# PiPico_Headless.net
KiCad netlist of a schematic drawn in EAGLE
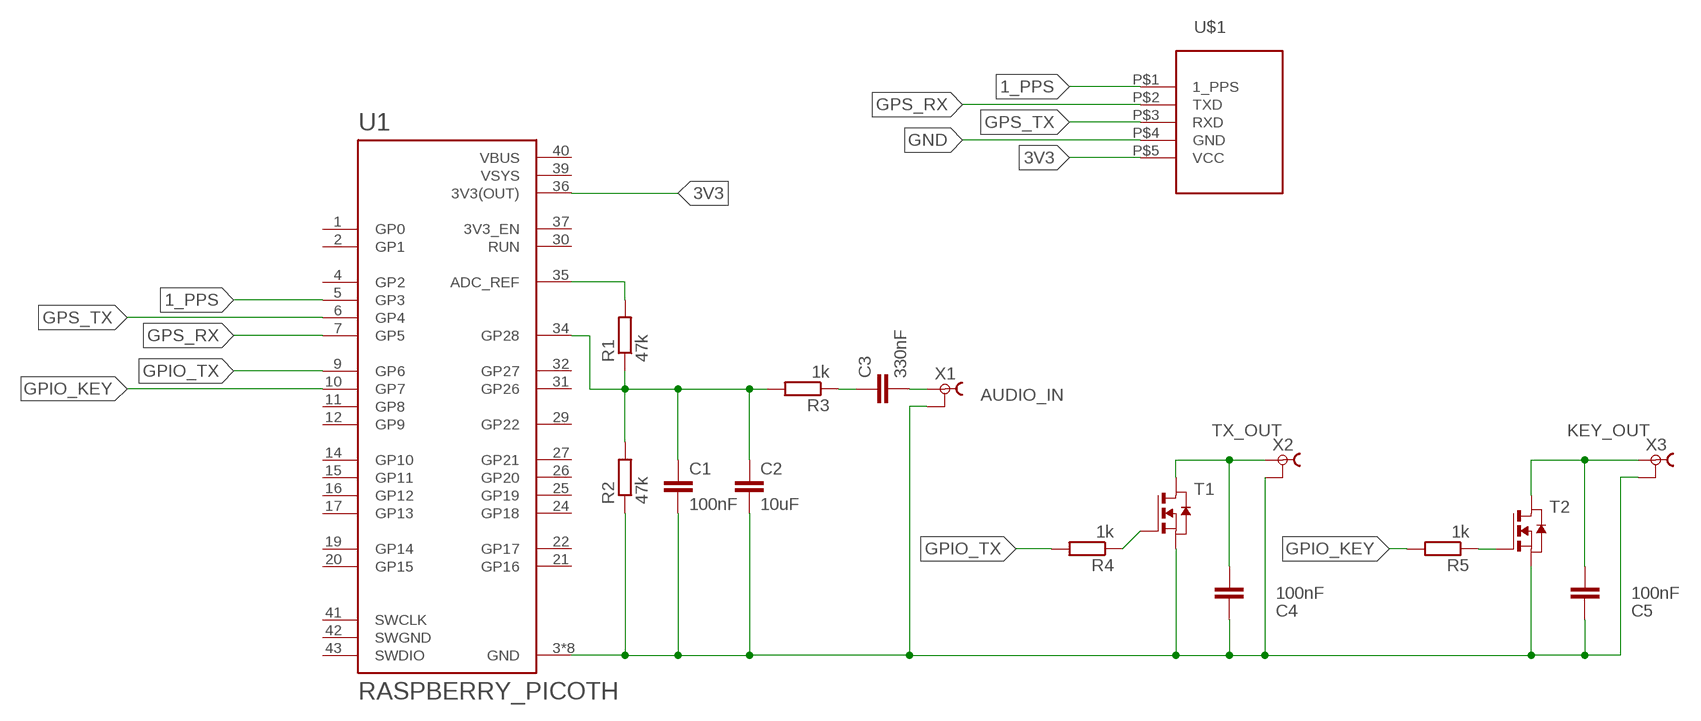
[diagram p0: schematic, sheet 1]

(export (version "E")
  (design (tool "Eeschema 10.0.6"))
  (components
    (comp (ref "C1")
      (value "100nF")
      (footprint "eagle-import:C0805")
      (libsource (lib "eagle-import") (part "C-EUC0805"))
    )
    (comp (ref "C2")
      (value "10uF")
      (footprint "eagle-import:C0805")
      (libsource (lib "eagle-import") (part "C-EUC0805"))
    )
    (comp (ref "C3")
      (value "330nF")
      (footprint "eagle-import:C0805")
      (libsource (lib "eagle-import") (part "C-EUC0805"))
    )
    (comp (ref "C4")
      (value "100nF")
      (footprint "eagle-import:C0805")
      (libsource (lib "eagle-import") (part "C-EUC0805"))
    )
    (comp (ref "C5")
      (value "100nF")
      (footprint "eagle-import:C0805")
      (libsource (lib "eagle-import") (part "C-EUC0805"))
    )
    (comp (ref "R1")
      (value "47k")
      (footprint "eagle-import:R0805")
      (libsource (lib "eagle-import") (part "R-EU_R0805"))
    )
    (comp (ref "R2")
      (value "47k")
      (footprint "eagle-import:R0805")
      (libsource (lib "eagle-import") (part "R-EU_R0805"))
    )
    (comp (ref "R3")
      (value "1k")
      (footprint "eagle-import:R0805")
      (libsource (lib "eagle-import") (part "R-EU_R0805"))
    )
    (comp (ref "R4")
      (value "1k")
      (footprint "eagle-import:R0805")
      (libsource (lib "eagle-import") (part "R-EU_R0805"))
    )
    (comp (ref "R5")
      (value "1k")
      (footprint "eagle-import:R0805")
      (libsource (lib "eagle-import") (part "R-EU_R0805"))
    )
    (comp (ref "T1")
      (value "NMOSSOT23")
      (footprint "eagle-import:SOT-23")
      (libsource (lib "eagle-import") (part "NMOSSOT23"))
    )
    (comp (ref "T2")
      (value "NMOSSOT23")
      (footprint "eagle-import:SOT-23")
      (libsource (lib "eagle-import") (part "NMOSSOT23"))
    )
    (comp (ref "U$1")
      (value "GPS")
      (footprint "eagle-import:GPS")
      (libsource (lib "eagle-import") (part "GPS"))
    )
    (comp (ref "U1")
      (value "RASPBERRY_PICOTH")
      (footprint "eagle-import:PICO-PKG-TH")
      (libsource (lib "eagle-import") (part "RASPBERRY_PICOTH"))
    )
    (comp (ref "X1")
      (value "AUDIO_IN")
      (footprint "eagle-import:TOBU3")
      (fields (field (name "MF") "FARNELL") (field (name "MPN") "TOBU 3"))
      (libsource (lib "eagle-import") (part "TOBU3"))
    )
    (comp (ref "X2")
      (value "TX_OUT")
      (footprint "eagle-import:TOBU3")
      (fields (field (name "MF") "FARNELL") (field (name "MPN") "TOBU 3"))
      (libsource (lib "eagle-import") (part "TOBU3"))
    )
    (comp (ref "X3")
      (value "KEY_OUT")
      (footprint "eagle-import:TOBU3")
      (fields
        (field (name "MF") "FARNELL")
        (field (name "MPN") "TOBU 3")
        (field (name "MF_1") "FARNELL")
        (field (name "MPN_1") "TOBU 3")
        (field (name "OC_FARNELL") "592791")
        (field (name "OC_NEWARK") "06WX5914")
      )
      (libsource (lib "eagle-import") (part "TOBU3"))
    )
  )
  (nets
    (net (code "1") (name "/SWGND") (class "Default")
      (node (ref "U1") (pin "42") (pinfunction "SWGND_42") (pintype "power_in"))
    )
    (net (code "2") (name "/VBUS") (class "Default")
      (node (ref "U1") (pin "40") (pinfunction "VBUS_40") (pintype "power_in"))
    )
    (net (code "3") (name "/VSYS") (class "Default")
      (node (ref "U1") (pin "39") (pinfunction "VSYS_39") (pintype "power_in"))
    )
    (net (code "4") (name "1_PPS") (class "Default")
      (node (ref "U$1") (pin "P$1") (pinfunction "1_PPS_P$1") (pintype "bidirectional"))
      (node (ref "U1") (pin "5") (pinfunction "GP3_5") (pintype "bidirectional"))
    )
    (net (code "5") (name "3V3") (class "Default")
      (node (ref "U$1") (pin "P$5") (pinfunction "VCC_P$5") (pintype "bidirectional"))
      (node (ref "U1") (pin "36") (pinfunction "3V3(OUT)_36") (pintype "power_in"))
    )
    (net (code "6") (name "GND") (class "Default")
      (node (ref "C1") (pin "2") (pinfunction "2_2") (pintype "passive"))
      (node (ref "C2") (pin "2") (pinfunction "2_2") (pintype "passive"))
      (node (ref "C4") (pin "1") (pinfunction "1_1") (pintype "passive"))
      (node (ref "C5") (pin "1") (pinfunction "1_1") (pintype "passive"))
      (node (ref "R2") (pin "1") (pinfunction "1_1") (pintype "passive"))
      (node (ref "T1") (pin "2") (pinfunction "S_2") (pintype "passive"))
      (node (ref "T2") (pin "2") (pinfunction "S_2") (pintype "passive"))
      (node (ref "U$1") (pin "P$4") (pinfunction "GND_P$4") (pintype "bidirectional"))
      (node (ref "U1") (pin "13") (pinfunction "GND_13") (pintype "power_in"))
      (node (ref "U1") (pin "18") (pinfunction "GND_18") (pintype "power_in"))
      (node (ref "U1") (pin "23") (pinfunction "GND_23") (pintype "power_in"))
      (node (ref "U1") (pin "28") (pinfunction "GND_28") (pintype "power_in"))
      (node (ref "U1") (pin "3") (pinfunction "GND_3") (pintype "power_in"))
      (node (ref "U1") (pin "33") (pinfunction "GND_33") (pintype "power_in"))
      (node (ref "U1") (pin "38") (pinfunction "GND_38") (pintype "power_in"))
      (node (ref "U1") (pin "8") (pinfunction "GND_8") (pintype "power_in"))
      (node (ref "X1") (pin "2") (pinfunction "2_2") (pintype "passive"))
      (node (ref "X1") (pin "2@1") (pinfunction "2_2@1") (pintype "passive"))
      (node (ref "X1") (pin "2@2") (pinfunction "2_2@2") (pintype "passive"))
      (node (ref "X2") (pin "2") (pinfunction "2_2") (pintype "passive"))
      (node (ref "X2") (pin "2@1") (pinfunction "2_2@1") (pintype "passive"))
      (node (ref "X2") (pin "2@2") (pinfunction "2_2@2") (pintype "passive"))
      (node (ref "X3") (pin "2") (pinfunction "2_2") (pintype "passive"))
      (node (ref "X3") (pin "2@1") (pinfunction "2_2@1") (pintype "passive"))
      (node (ref "X3") (pin "2@2") (pinfunction "2_2@2") (pintype "passive"))
    )
    (net (code "7") (name "GPIO_KEY") (class "Default")
      (node (ref "R5") (pin "2") (pinfunction "2_2") (pintype "passive"))
      (node (ref "U1") (pin "10") (pinfunction "GP7_10") (pintype "bidirectional"))
    )
    (net (code "8") (name "GPIO_TX") (class "Default")
      (node (ref "R4") (pin "2") (pinfunction "2_2") (pintype "passive"))
      (node (ref "U1") (pin "9") (pinfunction "GP6_9") (pintype "bidirectional"))
    )
    (net (code "9") (name "GPS_RX") (class "Default")
      (node (ref "U$1") (pin "P$2") (pinfunction "TXD_P$2") (pintype "bidirectional"))
      (node (ref "U1") (pin "7") (pinfunction "GP5_7") (pintype "bidirectional"))
    )
    (net (code "10") (name "GPS_TX") (class "Default")
      (node (ref "U$1") (pin "P$3") (pinfunction "RXD_P$3") (pintype "bidirectional"))
      (node (ref "U1") (pin "6") (pinfunction "GP4_6") (pintype "bidirectional"))
    )
    (net (code "11") (name "Net-(C3-Pad1)") (class "Default")
      (node (ref "C3") (pin "1") (pinfunction "1_1") (pintype "passive"))
      (node (ref "R3") (pin "1") (pinfunction "1_1") (pintype "passive"))
    )
    (net (code "12") (name "Net-(C3-Pad2)") (class "Default")
      (node (ref "C3") (pin "2") (pinfunction "2_2") (pintype "passive"))
      (node (ref "X1") (pin "1") (pinfunction "1_1") (pintype "passive"))
    )
    (net (code "13") (name "Net-(T1-D)") (class "Default")
      (node (ref "C4") (pin "2") (pinfunction "2_2") (pintype "passive"))
      (node (ref "T1") (pin "1") (pinfunction "D_1") (pintype "passive"))
      (node (ref "X2") (pin "1") (pinfunction "1_1") (pintype "passive"))
    )
    (net (code "14") (name "Net-(T1-G)") (class "Default")
      (node (ref "R4") (pin "1") (pinfunction "1_1") (pintype "passive"))
      (node (ref "T1") (pin "3") (pinfunction "G_3") (pintype "passive"))
    )
    (net (code "15") (name "Net-(T2-D)") (class "Default")
      (node (ref "C5") (pin "2") (pinfunction "2_2") (pintype "passive"))
      (node (ref "T2") (pin "1") (pinfunction "D_1") (pintype "passive"))
      (node (ref "X3") (pin "1") (pinfunction "1_1") (pintype "passive"))
    )
    (net (code "16") (name "Net-(T2-G)") (class "Default")
      (node (ref "R5") (pin "1") (pinfunction "1_1") (pintype "passive"))
      (node (ref "T2") (pin "3") (pinfunction "G_3") (pintype "passive"))
    )
    (net (code "17") (name "Net-(U1-ADC_REF)") (class "Default")
      (node (ref "R1") (pin "2") (pinfunction "2_2") (pintype "passive"))
      (node (ref "U1") (pin "35") (pinfunction "ADC_REF_35") (pintype "input"))
    )
    (net (code "18") (name "Net-(U1-GP28)") (class "Default")
      (node (ref "C1") (pin "1") (pinfunction "1_1") (pintype "passive"))
      (node (ref "C2") (pin "1") (pinfunction "1_1") (pintype "passive"))
      (node (ref "R1") (pin "1") (pinfunction "1_1") (pintype "passive"))
      (node (ref "R2") (pin "2") (pinfunction "2_2") (pintype "passive"))
      (node (ref "R3") (pin "2") (pinfunction "2_2") (pintype "passive"))
      (node (ref "U1") (pin "34") (pinfunction "GP28_34") (pintype "bidirectional"))
    )
    (net (code "19") (name "unconnected-(U1-3V3_EN-Pad37)") (class "Default")
      (node (ref "U1") (pin "37") (pinfunction "3V3_EN_37") (pintype "input"))
    )
    (net (code "20") (name "unconnected-(U1-GP0-Pad1)") (class "Default")
      (node (ref "U1") (pin "1") (pinfunction "GP0_1") (pintype "bidirectional"))
    )
    (net (code "21") (name "unconnected-(U1-GP1-Pad2)") (class "Default")
      (node (ref "U1") (pin "2") (pinfunction "GP1_2") (pintype "bidirectional"))
    )
    (net (code "22") (name "unconnected-(U1-GP2-Pad4)") (class "Default")
      (node (ref "U1") (pin "4") (pinfunction "GP2_4") (pintype "bidirectional"))
    )
    (net (code "23") (name "unconnected-(U1-GP8-Pad11)") (class "Default")
      (node (ref "U1") (pin "11") (pinfunction "GP8_11") (pintype "bidirectional"))
    )
    (net (code "24") (name "unconnected-(U1-GP9-Pad12)") (class "Default")
      (node (ref "U1") (pin "12") (pinfunction "GP9_12") (pintype "bidirectional"))
    )
    (net (code "25") (name "unconnected-(U1-GP10-Pad14)") (class "Default")
      (node (ref "U1") (pin "14") (pinfunction "GP10_14") (pintype "bidirectional"))
    )
    (net (code "26") (name "unconnected-(U1-GP11-Pad15)") (class "Default")
      (node (ref "U1") (pin "15") (pinfunction "GP11_15") (pintype "bidirectional"))
    )
    (net (code "27") (name "unconnected-(U1-GP12-Pad16)") (class "Default")
      (node (ref "U1") (pin "16") (pinfunction "GP12_16") (pintype "bidirectional"))
    )
    (net (code "28") (name "unconnected-(U1-GP13-Pad17)") (class "Default")
      (node (ref "U1") (pin "17") (pinfunction "GP13_17") (pintype "bidirectional"))
    )
    (net (code "29") (name "unconnected-(U1-GP14-Pad19)") (class "Default")
      (node (ref "U1") (pin "19") (pinfunction "GP14_19") (pintype "bidirectional"))
    )
    (net (code "30") (name "unconnected-(U1-GP15-Pad20)") (class "Default")
      (node (ref "U1") (pin "20") (pinfunction "GP15_20") (pintype "bidirectional"))
    )
    (net (code "31") (name "unconnected-(U1-GP16-Pad21)") (class "Default")
      (node (ref "U1") (pin "21") (pinfunction "GP16_21") (pintype "bidirectional"))
    )
    (net (code "32") (name "unconnected-(U1-GP17-Pad22)") (class "Default")
      (node (ref "U1") (pin "22") (pinfunction "GP17_22") (pintype "bidirectional"))
    )
    (net (code "33") (name "unconnected-(U1-GP18-Pad24)") (class "Default")
      (node (ref "U1") (pin "24") (pinfunction "GP18_24") (pintype "bidirectional"))
    )
    (net (code "34") (name "unconnected-(U1-GP19-Pad25)") (class "Default")
      (node (ref "U1") (pin "25") (pinfunction "GP19_25") (pintype "bidirectional"))
    )
    (net (code "35") (name "unconnected-(U1-GP20-Pad26)") (class "Default")
      (node (ref "U1") (pin "26") (pinfunction "GP20_26") (pintype "bidirectional"))
    )
    (net (code "36") (name "unconnected-(U1-GP21-Pad27)") (class "Default")
      (node (ref "U1") (pin "27") (pinfunction "GP21_27") (pintype "bidirectional"))
    )
    (net (code "37") (name "unconnected-(U1-GP22-Pad29)") (class "Default")
      (node (ref "U1") (pin "29") (pinfunction "GP22_29") (pintype "bidirectional"))
    )
    (net (code "38") (name "unconnected-(U1-GP26-Pad31)") (class "Default")
      (node (ref "U1") (pin "31") (pinfunction "GP26_31") (pintype "bidirectional"))
    )
    (net (code "39") (name "unconnected-(U1-GP27-Pad32)") (class "Default")
      (node (ref "U1") (pin "32") (pinfunction "GP27_32") (pintype "bidirectional"))
    )
    (net (code "40") (name "unconnected-(U1-RUN-Pad30)") (class "Default")
      (node (ref "U1") (pin "30") (pinfunction "RUN_30") (pintype "input"))
    )
    (net (code "41") (name "unconnected-(U1-SWCLK-Pad41)") (class "Default")
      (node (ref "U1") (pin "41") (pinfunction "SWCLK_41") (pintype "input"))
    )
    (net (code "42") (name "unconnected-(U1-SWDIO-Pad43)") (class "Default")
      (node (ref "U1") (pin "43") (pinfunction "SWDIO_43") (pintype "bidirectional"))
    )
  )
)
